# sensor.net
KiCad netlist of a schematic drawn in EAGLE
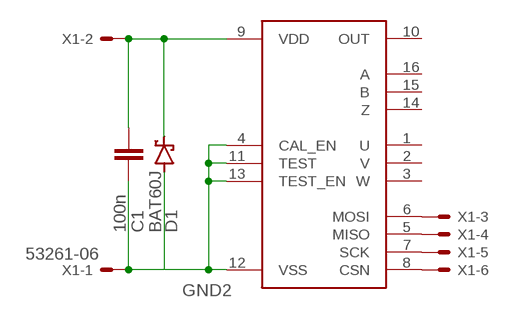
[diagram p0: schematic, sheet 1]

(export (version "E")
  (design (tool "Eeschema 10.0.6"))
  (components
    (comp (ref "C1")
      (value "100n")
      (footprint "eagle-import:C0603")
      (libsource (lib "eagle-import") (part "C-EUC0603"))
    )
    (comp (ref "D1")
      (value "BAT60J")
      (footprint "eagle-import:SOD323_ST")
      (libsource (lib "eagle-import") (part "BAT60J"))
    )
    (comp (ref "IC1")
      (value "MT6835")
      (footprint "eagle-import:TSSOP-16")
      (libsource (lib "eagle-import") (part "MT6835"))
    )
    (comp (ref "X1")
      (value "53261-06")
      (footprint "eagle-import:53261-06")
      (fields (field (name "MF") "MOLEX"))
      (libsource (lib "eagle-import") (part "53?-06261"))
    )
  )
  (nets
    (net (code "1") (name "/GND2") (class "Default")
      (node (ref "C1") (pin "2") (pinfunction "2_2") (pintype "passive"))
      (node (ref "D1") (pin "A") (pinfunction "A_A") (pintype "passive"))
      (node (ref "IC1") (pin "11") (pinfunction "TEST_11") (pintype "bidirectional"))
      (node (ref "IC1") (pin "12") (pinfunction "VSS_12") (pintype "power_in"))
      (node (ref "IC1") (pin "13") (pinfunction "TEST_EN_13") (pintype "bidirectional"))
      (node (ref "IC1") (pin "4") (pinfunction "CAL_EN_4") (pintype "bidirectional"))
      (node (ref "X1") (pin "1") (pinfunction "S_1") (pintype "passive"))
    )
    (net (code "2") (name "Net-(IC1-CSN)") (class "Default")
      (node (ref "IC1") (pin "8") (pinfunction "CSN_8") (pintype "bidirectional"))
      (node (ref "X1") (pin "6") (pinfunction "S_6") (pintype "passive"))
    )
    (net (code "3") (name "Net-(IC1-MISO)") (class "Default")
      (node (ref "IC1") (pin "5") (pinfunction "MISO_5") (pintype "bidirectional"))
      (node (ref "X1") (pin "4") (pinfunction "S_4") (pintype "passive"))
    )
    (net (code "4") (name "Net-(IC1-MOSI)") (class "Default")
      (node (ref "IC1") (pin "6") (pinfunction "MOSI_6") (pintype "bidirectional"))
      (node (ref "X1") (pin "3") (pinfunction "S_3") (pintype "passive"))
    )
    (net (code "5") (name "Net-(IC1-SCK)") (class "Default")
      (node (ref "IC1") (pin "7") (pinfunction "SCK_7") (pintype "bidirectional"))
      (node (ref "X1") (pin "5") (pinfunction "S_5") (pintype "passive"))
    )
    (net (code "6") (name "Net-(IC1-VDD)") (class "Default")
      (node (ref "C1") (pin "1") (pinfunction "1_1") (pintype "passive"))
      (node (ref "D1") (pin "C") (pinfunction "C_C") (pintype "passive"))
      (node (ref "IC1") (pin "9") (pinfunction "VDD_9") (pintype "power_in"))
      (node (ref "X1") (pin "2") (pinfunction "S_2") (pintype "passive"))
    )
    (net (code "7") (name "unconnected-(IC1-A-Pad16)") (class "Default")
      (node (ref "IC1") (pin "16") (pinfunction "A_16") (pintype "bidirectional"))
    )
    (net (code "8") (name "unconnected-(IC1-B-Pad15)") (class "Default")
      (node (ref "IC1") (pin "15") (pinfunction "B_15") (pintype "bidirectional"))
    )
    (net (code "9") (name "unconnected-(IC1-OUT-Pad10)") (class "Default")
      (node (ref "IC1") (pin "10") (pinfunction "OUT_10") (pintype "bidirectional"))
    )
    (net (code "10") (name "unconnected-(IC1-U-Pad1)") (class "Default")
      (node (ref "IC1") (pin "1") (pinfunction "U_1") (pintype "bidirectional"))
    )
    (net (code "11") (name "unconnected-(IC1-V-Pad2)") (class "Default")
      (node (ref "IC1") (pin "2") (pinfunction "V_2") (pintype "bidirectional"))
    )
    (net (code "12") (name "unconnected-(IC1-W-Pad3)") (class "Default")
      (node (ref "IC1") (pin "3") (pinfunction "W_3") (pintype "bidirectional"))
    )
    (net (code "13") (name "unconnected-(IC1-Z-Pad14)") (class "Default")
      (node (ref "IC1") (pin "14") (pinfunction "Z_14") (pintype "bidirectional"))
    )
  )
)
